# WaterLevelMonitor_v1-2.net
KiCad netlist of a schematic drawn in EAGLE
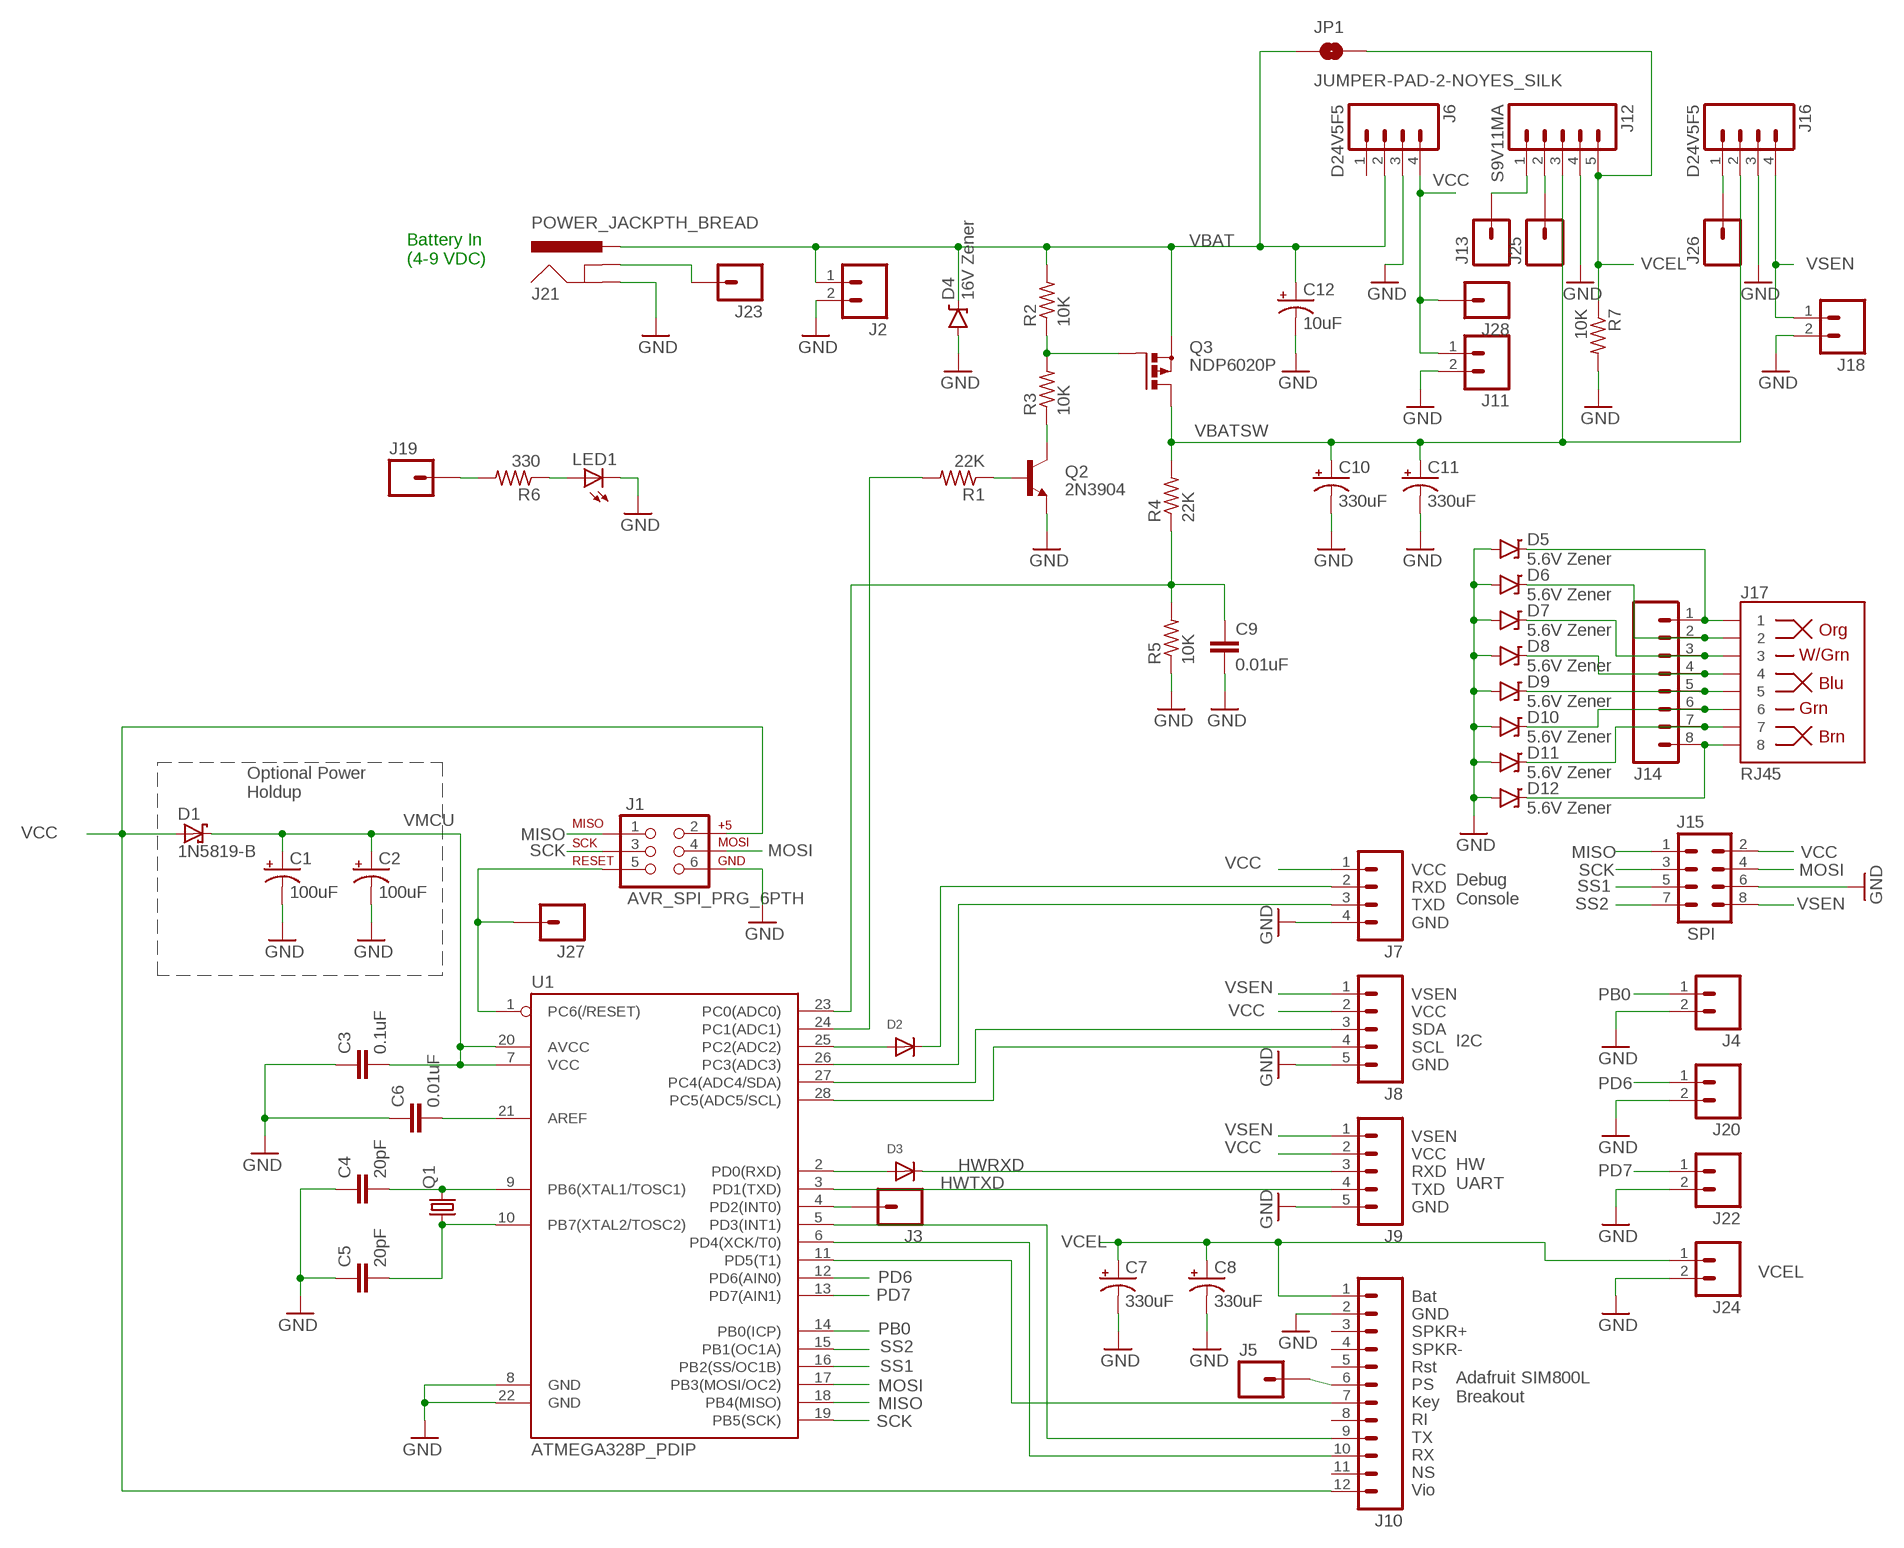
[diagram p0: schematic, sheet 1]

(export (version "E")
  (design (tool "Eeschema 10.0.6"))
  (components
    (comp (ref "C1")
      (value "100uF")
      (footprint "eagle-import:CPOL-RADIAL-100UF-25V")
      (libsource (lib "eagle-import") (part "CAP_POLPTH1"))
    )
    (comp (ref "C2")
      (value "100uF")
      (footprint "eagle-import:CPOL-RADIAL-100UF-25V")
      (libsource (lib "eagle-import") (part "CAP_POLPTH1"))
    )
    (comp (ref "C3")
      (value "0.1uF")
      (footprint "eagle-import:CAP-PTH-SMALL")
      (libsource (lib "eagle-import") (part "CAPPTH"))
    )
    (comp (ref "C4")
      (value "20pF")
      (footprint "eagle-import:CAP-PTH-SMALL")
      (libsource (lib "eagle-import") (part "CAPPTH"))
    )
    (comp (ref "C5")
      (value "20pF")
      (footprint "eagle-import:CAP-PTH-SMALL")
      (libsource (lib "eagle-import") (part "CAPPTH"))
    )
    (comp (ref "C6")
      (value "0.01uF")
      (footprint "eagle-import:CAP-PTH-5MM")
      (libsource (lib "eagle-import") (part "SparkFun-Passives_CAPPTH1"))
    )
    (comp (ref "C7")
      (value "330uF")
      (footprint "eagle-import:CPOL-RADIAL-100UF-25V")
      (libsource (lib "eagle-import") (part "CAP_POLPTH1"))
    )
    (comp (ref "C8")
      (value "330uF")
      (footprint "eagle-import:CPOL-RADIAL-100UF-25V")
      (libsource (lib "eagle-import") (part "CAP_POLPTH1"))
    )
    (comp (ref "C9")
      (value "0.01uF")
      (footprint "eagle-import:CAP-PTH-5MM")
      (libsource (lib "eagle-import") (part "SparkFun-Passives_CAPPTH1"))
    )
    (comp (ref "C10")
      (value "330uF")
      (footprint "eagle-import:CPOL-RADIAL-100UF-25V")
      (libsource (lib "eagle-import") (part "CAP_POLPTH1"))
    )
    (comp (ref "C11")
      (value "330uF")
      (footprint "eagle-import:CPOL-RADIAL-100UF-25V")
      (libsource (lib "eagle-import") (part "CAP_POLPTH1"))
    )
    (comp (ref "C12")
      (value "10uF")
      (footprint "eagle-import:CPOL-RADIAL-100UF-25V")
      (libsource (lib "eagle-import") (part "CAP_POLPTH1"))
    )
    (comp (ref "D1")
      (value "1N5819-B")
      (footprint "eagle-import:DO41-7.6")
      (libsource (lib "eagle-import") (part "1N5819-B"))
    )
    (comp (ref "D2")
      (value "DIODEDO-1N4148")
      (footprint "eagle-import:DO-1N4148")
      (libsource (lib "eagle-import") (part "DIODEDO-1N4148"))
    )
    (comp (ref "D3")
      (value "DIODEDO-1N4148")
      (footprint "eagle-import:DO-1N4148")
      (libsource (lib "eagle-import") (part "DIODEDO-1N4148"))
    )
    (comp (ref "D4")
      (value "16V Zener")
      (footprint "eagle-import:DIODE-ZENER")
      (libsource (lib "eagle-import") (part "DIODE-ZENERPTH"))
    )
    (comp (ref "D5")
      (value "5.6V Zener")
      (footprint "eagle-import:DIODE-ZENER")
      (libsource (lib "eagle-import") (part "DIODE-ZENERPTH"))
    )
    (comp (ref "D6")
      (value "5.6V Zener")
      (footprint "eagle-import:DIODE-ZENER")
      (libsource (lib "eagle-import") (part "DIODE-ZENERPTH"))
    )
    (comp (ref "D7")
      (value "5.6V Zener")
      (footprint "eagle-import:DIODE-ZENER")
      (libsource (lib "eagle-import") (part "DIODE-ZENERPTH"))
    )
    (comp (ref "D8")
      (value "5.6V Zener")
      (footprint "eagle-import:DIODE-ZENER")
      (libsource (lib "eagle-import") (part "DIODE-ZENERPTH"))
    )
    (comp (ref "D9")
      (value "5.6V Zener")
      (footprint "eagle-import:DIODE-ZENER")
      (libsource (lib "eagle-import") (part "DIODE-ZENERPTH"))
    )
    (comp (ref "D10")
      (value "5.6V Zener")
      (footprint "eagle-import:DIODE-ZENER")
      (libsource (lib "eagle-import") (part "DIODE-ZENERPTH"))
    )
    (comp (ref "D11")
      (value "5.6V Zener")
      (footprint "eagle-import:DIODE-ZENER")
      (libsource (lib "eagle-import") (part "DIODE-ZENERPTH"))
    )
    (comp (ref "D12")
      (value "5.6V Zener")
      (footprint "eagle-import:DIODE-ZENER")
      (libsource (lib "eagle-import") (part "DIODE-ZENERPTH"))
    )
    (comp (ref "J1")
      (value "AVR_SPI_PRG_6PTH")
      (footprint "eagle-import:2X3")
      (libsource (lib "eagle-import") (part "AVR_SPI_PRG_6PTH"))
    )
    (comp (ref "J2")
      (value "M02PTH")
      (footprint "eagle-import:1X02")
      (libsource (lib "eagle-import") (part "M02PTH"))
    )
    (comp (ref "J3")
      (value "M01PTH_NO_SILK_YES_STOP")
      (footprint "eagle-import:1X01_NO_SILK")
      (libsource (lib "eagle-import") (part "M01PTH_NO_SILK_YES_STOP"))
    )
    (comp (ref "J4")
      (value "M021X02_NO_SILK")
      (footprint "eagle-import:1X02_NO_SILK")
      (libsource (lib "eagle-import") (part "M021X02_NO_SILK"))
    )
    (comp (ref "J5")
      (value "M01PTH_NO_SILK_YES_STOP")
      (footprint "eagle-import:1X01_NO_SILK")
      (libsource (lib "eagle-import") (part "M01PTH_NO_SILK_YES_STOP"))
    )
    (comp (ref "J6")
      (value "D24V5F5")
      (footprint "eagle-import:1X04")
      (libsource (lib "eagle-import") (part "M04PTH"))
    )
    (comp (ref "J7")
      (value "M04PTH")
      (footprint "eagle-import:1X04")
      (libsource (lib "eagle-import") (part "M04PTH"))
    )
    (comp (ref "J8")
      (value "M05PTH")
      (footprint "eagle-import:1X05")
      (libsource (lib "eagle-import") (part "M05PTH"))
    )
    (comp (ref "J9")
      (value "M05PTH")
      (footprint "eagle-import:1X05")
      (libsource (lib "eagle-import") (part "M05PTH"))
    )
    (comp (ref "J10")
      (value "M12PTH")
      (footprint "eagle-import:1X12")
      (libsource (lib "eagle-import") (part "M12PTH"))
    )
    (comp (ref "J11")
      (value "M02PTH")
      (footprint "eagle-import:1X02")
      (libsource (lib "eagle-import") (part "M02PTH"))
    )
    (comp (ref "J12")
      (value "S9V11MA")
      (footprint "eagle-import:1X05")
      (libsource (lib "eagle-import") (part "M05PTH"))
    )
    (comp (ref "J13")
      (value "M01PTH_NO_SILK_YES_STOP")
      (footprint "eagle-import:1X01_NO_SILK")
      (libsource (lib "eagle-import") (part "M01PTH_NO_SILK_YES_STOP"))
    )
    (comp (ref "J14")
      (value "M08SILK_FEMALE_PTH")
      (footprint "eagle-import:1X08")
      (libsource (lib "eagle-import") (part "M08SILK_FEMALE_PTH"))
    )
    (comp (ref "J15")
      (value "M04X2")
      (footprint "eagle-import:2X4")
      (libsource (lib "eagle-import") (part "M04X2"))
    )
    (comp (ref "J16")
      (value "D24V5F5")
      (footprint "eagle-import:1X04")
      (libsource (lib "eagle-import") (part "M04PTH"))
    )
    (comp (ref "J17")
      (value "RJ45")
      (footprint "eagle-import:RJ45-8")
      (libsource (lib "eagle-import") (part "RJ45-8PTH"))
    )
    (comp (ref "J18")
      (value "M02PTH")
      (footprint "eagle-import:1X02")
      (libsource (lib "eagle-import") (part "M02PTH"))
    )
    (comp (ref "J19")
      (value "M01PTH_NO_SILK_YES_STOP")
      (footprint "eagle-import:1X01_NO_SILK")
      (libsource (lib "eagle-import") (part "M01PTH_NO_SILK_YES_STOP"))
    )
    (comp (ref "J20")
      (value "M021X02_NO_SILK")
      (footprint "eagle-import:1X02_NO_SILK")
      (libsource (lib "eagle-import") (part "M021X02_NO_SILK"))
    )
    (comp (ref "J21")
      (value "POWER_JACKPTH_BREAD")
      (footprint "eagle-import:POWER_JACK_PTH_BREAD")
      (libsource (lib "eagle-import") (part "POWER_JACKPTH_BREAD"))
    )
    (comp (ref "J22")
      (value "M021X02_NO_SILK")
      (footprint "eagle-import:1X02_NO_SILK")
      (libsource (lib "eagle-import") (part "M021X02_NO_SILK"))
    )
    (comp (ref "J23")
      (value "M01PTH_NO_SILK_YES_STOP")
      (footprint "eagle-import:1X01_NO_SILK")
      (libsource (lib "eagle-import") (part "M01PTH_NO_SILK_YES_STOP"))
    )
    (comp (ref "J24")
      (value "M02PTH")
      (footprint "eagle-import:1X02")
      (libsource (lib "eagle-import") (part "M02PTH"))
    )
    (comp (ref "J25")
      (value "M01PTH_NO_SILK_YES_STOP")
      (footprint "eagle-import:1X01_NO_SILK")
      (libsource (lib "eagle-import") (part "M01PTH_NO_SILK_YES_STOP"))
    )
    (comp (ref "J26")
      (value "M01PTH_NO_SILK_YES_STOP")
      (footprint "eagle-import:1X01_NO_SILK")
      (libsource (lib "eagle-import") (part "M01PTH_NO_SILK_YES_STOP"))
    )
    (comp (ref "J27")
      (value "M01PTH_NO_SILK_YES_STOP")
      (footprint "eagle-import:1X01_NO_SILK")
      (libsource (lib "eagle-import") (part "M01PTH_NO_SILK_YES_STOP"))
    )
    (comp (ref "J28")
      (value "M01PTH_NO_SILK_YES_STOP")
      (footprint "eagle-import:1X01_NO_SILK")
      (libsource (lib "eagle-import") (part "M01PTH_NO_SILK_YES_STOP"))
    )
    (comp (ref "JP1")
      (value "JUMPER-PAD-2-NOYES_SILK")
      (footprint "eagle-import:PAD-JUMPER-2-NO_YES_SILK")
      (libsource (lib "eagle-import") (part "JUMPER-PAD-2-NOYES_SILK"))
    )
    (comp (ref "LED1")
      (value "LED5MM")
      (footprint "eagle-import:LED5MM")
      (libsource (lib "eagle-import") (part "LED5MM"))
    )
    (comp (ref "Q1")
      (value "CRYSTALHC49U-V")
      (footprint "eagle-import:HC49U-V")
      (libsource (lib "eagle-import") (part "CRYSTALHC49U-V"))
    )
    (comp (ref "Q2")
      (value "2N3904")
      (footprint "eagle-import:TO-92-AMMO")
      (libsource (lib "eagle-import") (part "TRANSISTOR_NPNTO-92-AMMO"))
    )
    (comp (ref "Q3")
      (value "NDP6020P")
      (footprint "eagle-import:TO220BV")
      (libsource (lib "eagle-import") (part "PMOSFET_PTO220BV"))
    )
    (comp (ref "R1")
      (value "22K")
      (footprint "eagle-import:0204_5")
      (libsource (lib "eagle-import") (part "R-US_0204/5"))
    )
    (comp (ref "R2")
      (value "10K")
      (footprint "eagle-import:0204_5")
      (libsource (lib "eagle-import") (part "R-US_0204/5"))
    )
    (comp (ref "R3")
      (value "10K")
      (footprint "eagle-import:0204_5")
      (libsource (lib "eagle-import") (part "R-US_0204/5"))
    )
    (comp (ref "R4")
      (value "22K")
      (footprint "eagle-import:0204_5")
      (libsource (lib "eagle-import") (part "R-US_0204/5"))
    )
    (comp (ref "R5")
      (value "10K")
      (footprint "eagle-import:0204_5")
      (libsource (lib "eagle-import") (part "R-US_0204/5"))
    )
    (comp (ref "R6")
      (value "330")
      (footprint "eagle-import:0204_5")
      (libsource (lib "eagle-import") (part "R-US_0204/5"))
    )
    (comp (ref "R7")
      (value "10K")
      (footprint "eagle-import:0204_5")
      (libsource (lib "eagle-import") (part "R-US_0204/5"))
    )
    (comp (ref "U1")
      (value "ATMEGA328P_PDIP")
      (footprint "eagle-import:DIL28-3")
      (libsource (lib "eagle-import") (part "ATMEGA328P_PDIP"))
    )
  )
  (nets
    (net (code "1") (name "/HWRXD") (class "Default")
      (node (ref "D3") (pin "C") (pinfunction "C_C") (pintype "passive"))
      (node (ref "J9") (pin "3") (pinfunction "3_3") (pintype "passive"))
    )
    (net (code "2") (name "/HWTXD") (class "Default")
      (node (ref "J9") (pin "4") (pinfunction "4_4") (pintype "passive"))
      (node (ref "U1") (pin "3") (pinfunction "PD1(TXD)_3") (pintype "bidirectional"))
    )
    (net (code "3") (name "/MISO") (class "Default")
      (node (ref "J1") (pin "1") (pinfunction "1_1") (pintype "passive"))
      (node (ref "J15") (pin "1") (pinfunction "1_1") (pintype "passive"))
      (node (ref "U1") (pin "18") (pinfunction "PB4(MISO)_18") (pintype "bidirectional"))
    )
    (net (code "4") (name "/MOSI") (class "Default")
      (node (ref "J1") (pin "4") (pinfunction "4_4") (pintype "passive"))
      (node (ref "J15") (pin "4") (pinfunction "4_4") (pintype "passive"))
      (node (ref "U1") (pin "17") (pinfunction "PB3(MOSI/OC2)_17") (pintype "bidirectional"))
    )
    (net (code "5") (name "/PB0") (class "Default")
      (node (ref "J4") (pin "1") (pinfunction "1_1") (pintype "passive"))
      (node (ref "U1") (pin "14") (pinfunction "PB0(ICP)_14") (pintype "bidirectional"))
    )
    (net (code "6") (name "/PD6") (class "Default")
      (node (ref "J20") (pin "1") (pinfunction "1_1") (pintype "passive"))
      (node (ref "U1") (pin "12") (pinfunction "PD6(AIN0)_12") (pintype "bidirectional"))
    )
    (net (code "7") (name "/PD7") (class "Default")
      (node (ref "J22") (pin "1") (pinfunction "1_1") (pintype "passive"))
      (node (ref "U1") (pin "13") (pinfunction "PD7(AIN1)_13") (pintype "bidirectional"))
    )
    (net (code "8") (name "/SCK") (class "Default")
      (node (ref "J1") (pin "3") (pinfunction "3_3") (pintype "passive"))
      (node (ref "J15") (pin "3") (pinfunction "3_3") (pintype "passive"))
      (node (ref "U1") (pin "19") (pinfunction "PB5(SCK)_19") (pintype "bidirectional"))
    )
    (net (code "9") (name "/SS1") (class "Default")
      (node (ref "J15") (pin "5") (pinfunction "5_5") (pintype "passive"))
      (node (ref "U1") (pin "16") (pinfunction "PB2(SS/OC1B)_16") (pintype "bidirectional"))
    )
    (net (code "10") (name "/SS2") (class "Default")
      (node (ref "J15") (pin "7") (pinfunction "7_7") (pintype "passive"))
      (node (ref "U1") (pin "15") (pinfunction "PB1(OC1A)_15") (pintype "bidirectional"))
    )
    (net (code "11") (name "/VBAT") (class "Default")
      (node (ref "C12") (pin "1") (pinfunction "+_1") (pintype "passive"))
      (node (ref "D4") (pin "P$1") (pinfunction "C_P$1") (pintype "passive"))
      (node (ref "J2") (pin "1") (pinfunction "1_1") (pintype "passive"))
      (node (ref "J21") (pin "PWR") (pinfunction "PWR_PWR") (pintype "bidirectional"))
      (node (ref "J6") (pin "2") (pinfunction "2_2") (pintype "passive"))
      (node (ref "JP1") (pin "1") (pinfunction "1_1") (pintype "passive"))
      (node (ref "Q3") (pin "S") (pinfunction "S_S") (pintype "passive"))
      (node (ref "R2") (pin "2") (pinfunction "2_2") (pintype "passive"))
    )
    (net (code "12") (name "/VBATSW") (class "Default")
      (node (ref "C10") (pin "1") (pinfunction "+_1") (pintype "passive"))
      (node (ref "C11") (pin "1") (pinfunction "+_1") (pintype "passive"))
      (node (ref "J12") (pin "3") (pinfunction "3_3") (pintype "passive"))
      (node (ref "J16") (pin "2") (pinfunction "2_2") (pintype "passive"))
      (node (ref "Q3") (pin "D") (pinfunction "D_D") (pintype "passive"))
      (node (ref "R4") (pin "2") (pinfunction "2_2") (pintype "passive"))
    )
    (net (code "13") (name "/VCC") (class "Default")
      (node (ref "D1") (pin "A") (pinfunction "A_A") (pintype "passive"))
      (node (ref "J1") (pin "2") (pinfunction "2_2") (pintype "passive"))
      (node (ref "J10") (pin "12") (pinfunction "12_12") (pintype "passive"))
      (node (ref "J11") (pin "1") (pinfunction "1_1") (pintype "passive"))
      (node (ref "J15") (pin "2") (pinfunction "2_2") (pintype "passive"))
      (node (ref "J28") (pin "1") (pinfunction "1_1") (pintype "passive"))
      (node (ref "J6") (pin "4") (pinfunction "4_4") (pintype "passive"))
      (node (ref "J7") (pin "1") (pinfunction "1_1") (pintype "passive"))
      (node (ref "J8") (pin "2") (pinfunction "2_2") (pintype "passive"))
      (node (ref "J9") (pin "2") (pinfunction "2_2") (pintype "passive"))
    )
    (net (code "14") (name "/VCEL") (class "Default")
      (node (ref "C7") (pin "1") (pinfunction "+_1") (pintype "passive"))
      (node (ref "C8") (pin "1") (pinfunction "+_1") (pintype "passive"))
      (node (ref "J10") (pin "1") (pinfunction "1_1") (pintype "passive"))
      (node (ref "J12") (pin "5") (pinfunction "5_5") (pintype "passive"))
      (node (ref "J24") (pin "1") (pinfunction "1_1") (pintype "passive"))
      (node (ref "JP1") (pin "2") (pinfunction "2_2") (pintype "passive"))
      (node (ref "R7") (pin "1") (pinfunction "1_1") (pintype "passive"))
    )
    (net (code "15") (name "/VMCU") (class "Default")
      (node (ref "C1") (pin "1") (pinfunction "+_1") (pintype "passive"))
      (node (ref "C2") (pin "1") (pinfunction "+_1") (pintype "passive"))
      (node (ref "C3") (pin "2") (pinfunction "2_2") (pintype "passive"))
      (node (ref "D1") (pin "C") (pinfunction "C_C") (pintype "passive"))
      (node (ref "U1") (pin "20") (pinfunction "AVCC_20") (pintype "bidirectional"))
      (node (ref "U1") (pin "7") (pinfunction "VCC_7") (pintype "bidirectional"))
    )
    (net (code "16") (name "/VSEN") (class "Default")
      (node (ref "J15") (pin "8") (pinfunction "8_8") (pintype "passive"))
      (node (ref "J16") (pin "4") (pinfunction "4_4") (pintype "passive"))
      (node (ref "J18") (pin "1") (pinfunction "1_1") (pintype "passive"))
      (node (ref "J8") (pin "1") (pinfunction "1_1") (pintype "passive"))
      (node (ref "J9") (pin "1") (pinfunction "1_1") (pintype "passive"))
    )
    (net (code "17") (name "GND") (class "Default")
      (node (ref "C1") (pin "2") (pinfunction "-_2") (pintype "passive"))
      (node (ref "C10") (pin "2") (pinfunction "-_2") (pintype "passive"))
      (node (ref "C11") (pin "2") (pinfunction "-_2") (pintype "passive"))
      (node (ref "C12") (pin "2") (pinfunction "-_2") (pintype "passive"))
      (node (ref "C2") (pin "2") (pinfunction "-_2") (pintype "passive"))
      (node (ref "C3") (pin "1") (pinfunction "1_1") (pintype "passive"))
      (node (ref "C4") (pin "1") (pinfunction "1_1") (pintype "passive"))
      (node (ref "C5") (pin "1") (pinfunction "1_1") (pintype "passive"))
      (node (ref "C6") (pin "1") (pinfunction "1_1") (pintype "passive"))
      (node (ref "C7") (pin "2") (pinfunction "-_2") (pintype "passive"))
      (node (ref "C8") (pin "2") (pinfunction "-_2") (pintype "passive"))
      (node (ref "C9") (pin "2") (pinfunction "2_2") (pintype "passive"))
      (node (ref "D10") (pin "P$2") (pinfunction "A_P$2") (pintype "passive"))
      (node (ref "D11") (pin "P$2") (pinfunction "A_P$2") (pintype "passive"))
      (node (ref "D12") (pin "P$2") (pinfunction "A_P$2") (pintype "passive"))
      (node (ref "D4") (pin "P$2") (pinfunction "A_P$2") (pintype "passive"))
      (node (ref "D5") (pin "P$2") (pinfunction "A_P$2") (pintype "passive"))
      (node (ref "D6") (pin "P$2") (pinfunction "A_P$2") (pintype "passive"))
      (node (ref "D7") (pin "P$2") (pinfunction "A_P$2") (pintype "passive"))
      (node (ref "D8") (pin "P$2") (pinfunction "A_P$2") (pintype "passive"))
      (node (ref "D9") (pin "P$2") (pinfunction "A_P$2") (pintype "passive"))
      (node (ref "J1") (pin "6") (pinfunction "6_6") (pintype "passive"))
      (node (ref "J10") (pin "2") (pinfunction "2_2") (pintype "passive"))
      (node (ref "J11") (pin "2") (pinfunction "2_2") (pintype "passive"))
      (node (ref "J12") (pin "4") (pinfunction "4_4") (pintype "passive"))
      (node (ref "J15") (pin "6") (pinfunction "6_6") (pintype "passive"))
      (node (ref "J16") (pin "3") (pinfunction "3_3") (pintype "passive"))
      (node (ref "J18") (pin "2") (pinfunction "2_2") (pintype "passive"))
      (node (ref "J2") (pin "2") (pinfunction "2_2") (pintype "passive"))
      (node (ref "J20") (pin "2") (pinfunction "2_2") (pintype "passive"))
      (node (ref "J21") (pin "GND") (pinfunction "GND_GND") (pintype "bidirectional"))
      (node (ref "J22") (pin "2") (pinfunction "2_2") (pintype "passive"))
      (node (ref "J24") (pin "2") (pinfunction "2_2") (pintype "passive"))
      (node (ref "J4") (pin "2") (pinfunction "2_2") (pintype "passive"))
      (node (ref "J6") (pin "3") (pinfunction "3_3") (pintype "passive"))
      (node (ref "J7") (pin "4") (pinfunction "4_4") (pintype "passive"))
      (node (ref "J8") (pin "5") (pinfunction "5_5") (pintype "passive"))
      (node (ref "J9") (pin "5") (pinfunction "5_5") (pintype "passive"))
      (node (ref "LED1") (pin "K") (pinfunction "C_K") (pintype "passive"))
      (node (ref "Q2") (pin "1") (pinfunction "E_1") (pintype "passive"))
      (node (ref "R5") (pin "1") (pinfunction "1_1") (pintype "passive"))
      (node (ref "R7") (pin "2") (pinfunction "2_2") (pintype "passive"))
      (node (ref "U1") (pin "22") (pinfunction "GND_22") (pintype "bidirectional"))
      (node (ref "U1") (pin "8") (pinfunction "GND_8") (pintype "bidirectional"))
    )
    (net (code "18") (name "Net-(D2-PadC)") (class "Default")
      (node (ref "D2") (pin "C") (pinfunction "C_C") (pintype "passive"))
      (node (ref "J7") (pin "2") (pinfunction "2_2") (pintype "passive"))
    )
    (net (code "19") (name "Net-(D5-C)") (class "Default")
      (node (ref "D5") (pin "P$1") (pinfunction "C_P$1") (pintype "passive"))
      (node (ref "J14") (pin "1") (pinfunction "1_1") (pintype "passive"))
      (node (ref "J17") (pin "1") (pinfunction "1_1") (pintype "bidirectional"))
    )
    (net (code "20") (name "Net-(D6-C)") (class "Default")
      (node (ref "D6") (pin "P$1") (pinfunction "C_P$1") (pintype "passive"))
      (node (ref "J14") (pin "2") (pinfunction "2_2") (pintype "passive"))
      (node (ref "J17") (pin "2") (pinfunction "2_2") (pintype "bidirectional"))
    )
    (net (code "21") (name "Net-(D7-C)") (class "Default")
      (node (ref "D7") (pin "P$1") (pinfunction "C_P$1") (pintype "passive"))
      (node (ref "J14") (pin "3") (pinfunction "3_3") (pintype "passive"))
      (node (ref "J17") (pin "3") (pinfunction "3_3") (pintype "bidirectional"))
    )
    (net (code "22") (name "Net-(D8-C)") (class "Default")
      (node (ref "D8") (pin "P$1") (pinfunction "C_P$1") (pintype "passive"))
      (node (ref "J14") (pin "4") (pinfunction "4_4") (pintype "passive"))
      (node (ref "J17") (pin "4") (pinfunction "4_4") (pintype "bidirectional"))
    )
    (net (code "23") (name "Net-(D9-C)") (class "Default")
      (node (ref "D9") (pin "P$1") (pinfunction "C_P$1") (pintype "passive"))
      (node (ref "J14") (pin "5") (pinfunction "5_5") (pintype "passive"))
      (node (ref "J17") (pin "5") (pinfunction "5_5") (pintype "bidirectional"))
    )
    (net (code "24") (name "Net-(D10-C)") (class "Default")
      (node (ref "D10") (pin "P$1") (pinfunction "C_P$1") (pintype "passive"))
      (node (ref "J14") (pin "6") (pinfunction "6_6") (pintype "passive"))
      (node (ref "J17") (pin "6") (pinfunction "6_6") (pintype "bidirectional"))
    )
    (net (code "25") (name "Net-(D11-C)") (class "Default")
      (node (ref "D11") (pin "P$1") (pinfunction "C_P$1") (pintype "passive"))
      (node (ref "J14") (pin "7") (pinfunction "7_7") (pintype "passive"))
      (node (ref "J17") (pin "7") (pinfunction "7_7") (pintype "bidirectional"))
    )
    (net (code "26") (name "Net-(D12-C)") (class "Default")
      (node (ref "D12") (pin "P$1") (pinfunction "C_P$1") (pintype "passive"))
      (node (ref "J14") (pin "8") (pinfunction "8_8") (pintype "passive"))
      (node (ref "J17") (pin "8") (pinfunction "8_8") (pintype "bidirectional"))
    )
    (net (code "27") (name "Net-(J10-Pad6)") (class "Default")
      (node (ref "J10") (pin "6") (pinfunction "6_6") (pintype "passive"))
      (node (ref "J5") (pin "1") (pinfunction "1_1") (pintype "passive"))
    )
    (net (code "28") (name "Net-(J12-Pad1)") (class "Default")
      (node (ref "J12") (pin "1") (pinfunction "1_1") (pintype "passive"))
      (node (ref "J13") (pin "1") (pinfunction "1_1") (pintype "passive"))
    )
    (net (code "29") (name "Net-(J12-Pad2)") (class "Default")
      (node (ref "J12") (pin "2") (pinfunction "2_2") (pintype "passive"))
      (node (ref "J25") (pin "1") (pinfunction "1_1") (pintype "passive"))
    )
    (net (code "30") (name "Net-(J16-Pad1)") (class "Default")
      (node (ref "J16") (pin "1") (pinfunction "1_1") (pintype "passive"))
      (node (ref "J26") (pin "1") (pinfunction "1_1") (pintype "passive"))
    )
    (net (code "31") (name "Net-(J19-Pad1)") (class "Default")
      (node (ref "J19") (pin "1") (pinfunction "1_1") (pintype "passive"))
      (node (ref "R6") (pin "2") (pinfunction "2_2") (pintype "passive"))
    )
    (net (code "32") (name "Net-(J21-PadGNDBREAK)") (class "Default")
      (node (ref "J21") (pin "GNDBREAK") (pinfunction "GNDBREAK_GNDBREAK") (pintype "bidirectional"))
      (node (ref "J23") (pin "1") (pinfunction "1_1") (pintype "passive"))
    )
    (net (code "33") (name "Net-(LED1-PadA)") (class "Default")
      (node (ref "LED1") (pin "A") (pinfunction "A_A") (pintype "passive"))
      (node (ref "R6") (pin "1") (pinfunction "1_1") (pintype "passive"))
    )
    (net (code "34") (name "Net-(Q2-B)") (class "Default")
      (node (ref "Q2") (pin "2") (pinfunction "B_2") (pintype "passive"))
      (node (ref "R1") (pin "1") (pinfunction "1_1") (pintype "passive"))
    )
    (net (code "35") (name "Net-(Q2-C)") (class "Default")
      (node (ref "Q2") (pin "3") (pinfunction "C_3") (pintype "passive"))
      (node (ref "R3") (pin "1") (pinfunction "1_1") (pintype "passive"))
    )
    (net (code "36") (name "Net-(Q3-PadG)") (class "Default")
      (node (ref "Q3") (pin "G") (pinfunction "G_G") (pintype "passive"))
      (node (ref "R2") (pin "1") (pinfunction "1_1") (pintype "passive"))
      (node (ref "R3") (pin "2") (pinfunction "2_2") (pintype "passive"))
    )
    (net (code "37") (name "Net-(U1-AREF)") (class "Default")
      (node (ref "C6") (pin "2") (pinfunction "2_2") (pintype "passive"))
      (node (ref "U1") (pin "21") (pinfunction "AREF_21") (pintype "bidirectional"))
    )
    (net (code "38") (name "Net-(U1-PB6(XTAL1{slash}TOSC1))") (class "Default")
      (node (ref "C4") (pin "2") (pinfunction "2_2") (pintype "passive"))
      (node (ref "Q1") (pin "2") (pinfunction "2_2") (pintype "passive"))
      (node (ref "U1") (pin "9") (pinfunction "PB6(XTAL1/TOSC1)_9") (pintype "bidirectional"))
    )
    (net (code "39") (name "Net-(U1-PB7(XTAL2{slash}TOSC2))") (class "Default")
      (node (ref "C5") (pin "2") (pinfunction "2_2") (pintype "passive"))
      (node (ref "Q1") (pin "1") (pinfunction "1_1") (pintype "passive"))
      (node (ref "U1") (pin "10") (pinfunction "PB7(XTAL2/TOSC2)_10") (pintype "bidirectional"))
    )
    (net (code "40") (name "Net-(U1-PC0(ADC0))") (class "Default")
      (node (ref "C9") (pin "1") (pinfunction "1_1") (pintype "passive"))
      (node (ref "R4") (pin "1") (pinfunction "1_1") (pintype "passive"))
      (node (ref "R5") (pin "2") (pinfunction "2_2") (pintype "passive"))
      (node (ref "U1") (pin "23") (pinfunction "PC0(ADC0)_23") (pintype "bidirectional"))
    )
    (net (code "41") (name "Net-(U1-PC1(ADC1))") (class "Default")
      (node (ref "R1") (pin "2") (pinfunction "2_2") (pintype "passive"))
      (node (ref "U1") (pin "24") (pinfunction "PC1(ADC1)_24") (pintype "bidirectional"))
    )
    (net (code "42") (name "Net-(U1-PC2(ADC2))") (class "Default")
      (node (ref "D2") (pin "A") (pinfunction "A_A") (pintype "passive"))
      (node (ref "U1") (pin "25") (pinfunction "PC2(ADC2)_25") (pintype "bidirectional"))
    )
    (net (code "43") (name "Net-(U1-PC3(ADC3))") (class "Default")
      (node (ref "J7") (pin "3") (pinfunction "3_3") (pintype "passive"))
      (node (ref "U1") (pin "26") (pinfunction "PC3(ADC3)_26") (pintype "bidirectional"))
    )
    (net (code "44") (name "Net-(U1-PC4(ADC4{slash}SDA))") (class "Default")
      (node (ref "J8") (pin "3") (pinfunction "3_3") (pintype "passive"))
      (node (ref "U1") (pin "27") (pinfunction "PC4(ADC4/SDA)_27") (pintype "bidirectional"))
    )
    (net (code "45") (name "Net-(U1-PC5(ADC5{slash}SCL))") (class "Default")
      (node (ref "J8") (pin "4") (pinfunction "4_4") (pintype "passive"))
      (node (ref "U1") (pin "28") (pinfunction "PC5(ADC5/SCL)_28") (pintype "bidirectional"))
    )
    (net (code "46") (name "Net-(U1-PC6({slash}RESET))") (class "Default")
      (node (ref "J1") (pin "5") (pinfunction "5_5") (pintype "passive"))
      (node (ref "J27") (pin "1") (pinfunction "1_1") (pintype "passive"))
      (node (ref "U1") (pin "1") (pinfunction "PC6(/RESET)_1") (pintype "bidirectional"))
    )
    (net (code "47") (name "Net-(U1-PD0(RXD))") (class "Default")
      (node (ref "D3") (pin "A") (pinfunction "A_A") (pintype "passive"))
      (node (ref "U1") (pin "2") (pinfunction "PD0(RXD)_2") (pintype "bidirectional"))
    )
    (net (code "48") (name "Net-(U1-PD2(INT0))") (class "Default")
      (node (ref "J3") (pin "1") (pinfunction "1_1") (pintype "passive"))
      (node (ref "U1") (pin "4") (pinfunction "PD2(INT0)_4") (pintype "bidirectional"))
    )
    (net (code "49") (name "Net-(U1-PD3(INT1))") (class "Default")
      (node (ref "J10") (pin "9") (pinfunction "9_9") (pintype "passive"))
      (node (ref "U1") (pin "5") (pinfunction "PD3(INT1)_5") (pintype "bidirectional"))
    )
    (net (code "50") (name "Net-(U1-PD4(XCK{slash}T0))") (class "Default")
      (node (ref "J10") (pin "10") (pinfunction "10_10") (pintype "passive"))
      (node (ref "U1") (pin "6") (pinfunction "PD4(XCK/T0)_6") (pintype "bidirectional"))
    )
    (net (code "51") (name "Net-(U1-PD5(T1))") (class "Default")
      (node (ref "J10") (pin "7") (pinfunction "7_7") (pintype "passive"))
      (node (ref "U1") (pin "11") (pinfunction "PD5(T1)_11") (pintype "bidirectional"))
    )
    (net (code "52") (name "unconnected-(J6-Pad1)") (class "Default")
      (node (ref "J6") (pin "1") (pinfunction "1_1") (pintype "passive"))
    )
    (net (code "53") (name "unconnected-(J10-Pad3)") (class "Default")
      (node (ref "J10") (pin "3") (pinfunction "3_3") (pintype "passive"))
    )
    (net (code "54") (name "unconnected-(J10-Pad4)") (class "Default")
      (node (ref "J10") (pin "4") (pinfunction "4_4") (pintype "passive"))
    )
    (net (code "55") (name "unconnected-(J10-Pad5)") (class "Default")
      (node (ref "J10") (pin "5") (pinfunction "5_5") (pintype "passive"))
    )
    (net (code "56") (name "unconnected-(J10-Pad8)") (class "Default")
      (node (ref "J10") (pin "8") (pinfunction "8_8") (pintype "passive"))
    )
    (net (code "57") (name "unconnected-(J10-Pad11)") (class "Default")
      (node (ref "J10") (pin "11") (pinfunction "11_11") (pintype "passive"))
    )
  )
)
